# RLC_renonant.net
KiCad netlist of a schematic drawn in Altium Designer
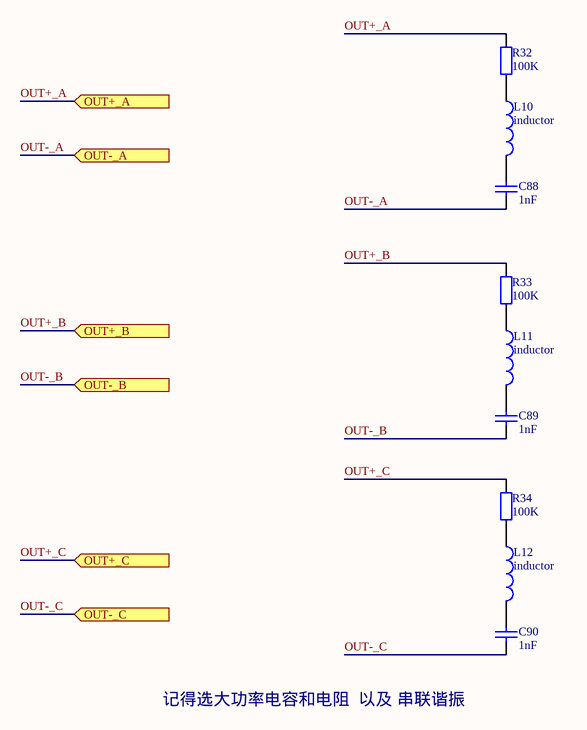
[diagram p0: RLC_renonant.SchDoc]

(export (version "E")
  (design (tool "Eeschema 10.0.6"))
  (components
    (comp (ref "C88") (value "1nF") (footprint "RAD-0.2") (libsource (lib "MyLibrary") (part "Cap")))
    (comp (ref "C89") (value "1nF") (footprint "RAD-0.2") (libsource (lib "MyLibrary") (part "Cap")))
    (comp (ref "C90") (value "1nF") (footprint "RAD-0.2") (libsource (lib "MyLibrary") (part "Cap")))
    (comp (ref "L10") (value "inductor") (footprint "inductor") (libsource (lib "Dugu") (part "inductor")))
    (comp (ref "L11") (value "inductor") (footprint "inductor") (libsource (lib "Dugu") (part "inductor")))
    (comp (ref "L12") (value "inductor") (footprint "inductor") (libsource (lib "Dugu") (part "inductor")))
    (comp (ref "R32")
      (value "100K")
      (footprint "Res_big")
      (fields
        (field (name "Comment") "Res")
        (field (name "原理图绘制者") "刘永钦")
        (field (name "原理图提供者") "刘永钦")
        (field (name "原理图审核人1") "徐鹏飞")
        (field (name "封装0805绘制者") "刘永钦")
        (field (name "封装0805提供者") "刘永钦")
        (field (name "封装0805审核人1") "徐鹏飞")
        (field (name "原理图审核人2") "朱觉文")
        (field (name "封装0805审核人2") "朱觉文")
        (field (name "封装0603提供者") "刘永钦")
        (field (name "封装0603审核人2") "朱觉文")
        (field (name "封装0603审核人1") "徐鹏飞")
        (field (name "封装2512-RESC6332X06N审核人2") "朱觉文")
        (field (name "封装2512-RESC6332X06N提供者") "刘永钦")
        (field (name "封装2512-RESC6332X06N审核人1") "徐鹏飞")
        (field (name "封装0603绘制者") "刘永钦")
        (field (name "封装2512-RESC6332X06N绘制者") "刘永钦")
      )
      (libsource (lib "DuGu") (part "Res"))
    )
    (comp (ref "R33")
      (value "100K")
      (footprint "Res_big")
      (fields
        (field (name "Comment") "Res")
        (field (name "原理图绘制者") "刘永钦")
        (field (name "原理图提供者") "刘永钦")
        (field (name "原理图审核人1") "徐鹏飞")
        (field (name "封装0805绘制者") "刘永钦")
        (field (name "封装0805提供者") "刘永钦")
        (field (name "封装0805审核人1") "徐鹏飞")
        (field (name "原理图审核人2") "朱觉文")
        (field (name "封装0805审核人2") "朱觉文")
        (field (name "封装0603提供者") "刘永钦")
        (field (name "封装0603审核人2") "朱觉文")
        (field (name "封装0603审核人1") "徐鹏飞")
        (field (name "封装2512-RESC6332X06N审核人2") "朱觉文")
        (field (name "封装2512-RESC6332X06N提供者") "刘永钦")
        (field (name "封装2512-RESC6332X06N审核人1") "徐鹏飞")
        (field (name "封装0603绘制者") "刘永钦")
        (field (name "封装2512-RESC6332X06N绘制者") "刘永钦")
      )
      (libsource (lib "DuGu") (part "Res"))
    )
    (comp (ref "R34")
      (value "100K")
      (footprint "Res_big")
      (fields
        (field (name "Comment") "Res")
        (field (name "原理图绘制者") "刘永钦")
        (field (name "原理图提供者") "刘永钦")
        (field (name "原理图审核人1") "徐鹏飞")
        (field (name "封装0805绘制者") "刘永钦")
        (field (name "封装0805提供者") "刘永钦")
        (field (name "封装0805审核人1") "徐鹏飞")
        (field (name "原理图审核人2") "朱觉文")
        (field (name "封装0805审核人2") "朱觉文")
        (field (name "封装0603提供者") "刘永钦")
        (field (name "封装0603审核人2") "朱觉文")
        (field (name "封装0603审核人1") "徐鹏飞")
        (field (name "封装2512-RESC6332X06N审核人2") "朱觉文")
        (field (name "封装2512-RESC6332X06N提供者") "刘永钦")
        (field (name "封装2512-RESC6332X06N审核人1") "徐鹏飞")
        (field (name "封装0603绘制者") "刘永钦")
        (field (name "封装2512-RESC6332X06N绘制者") "刘永钦")
      )
      (libsource (lib "DuGu") (part "Res"))
    )
  )
  (nets
    (net (code "1") (name "/OUT+_A") (class "Default")
      (node (ref "R32") (pin "1") (pinfunction "1_1") (pintype "passive"))
    )
    (net (code "2") (name "/OUT+_B") (class "Default")
      (node (ref "R33") (pin "1") (pinfunction "1_1") (pintype "passive"))
    )
    (net (code "3") (name "/OUT+_C") (class "Default")
      (node (ref "R34") (pin "1") (pinfunction "1_1") (pintype "passive"))
    )
    (net (code "4") (name "/OUT-_A") (class "Default")
      (node (ref "C88") (pin "1") (pinfunction "1_1") (pintype "passive"))
    )
    (net (code "5") (name "/OUT-_B") (class "Default")
      (node (ref "C89") (pin "1") (pinfunction "1_1") (pintype "passive"))
    )
    (net (code "6") (name "/OUT-_C") (class "Default")
      (node (ref "C90") (pin "1") (pinfunction "1_1") (pintype "passive"))
    )
    (net (code "7") (name "Net-(C88-Pad2)") (class "Default")
      (node (ref "C88") (pin "2") (pinfunction "2_2") (pintype "passive"))
      (node (ref "L10") (pin "2") (pinfunction "2_2") (pintype "passive"))
    )
    (net (code "8") (name "Net-(C89-Pad2)") (class "Default")
      (node (ref "C89") (pin "2") (pinfunction "2_2") (pintype "passive"))
      (node (ref "L11") (pin "2") (pinfunction "2_2") (pintype "passive"))
    )
    (net (code "9") (name "Net-(C90-Pad2)") (class "Default")
      (node (ref "C90") (pin "2") (pinfunction "2_2") (pintype "passive"))
      (node (ref "L12") (pin "2") (pinfunction "2_2") (pintype "passive"))
    )
    (net (code "10") (name "Net-(L10-Pad1)") (class "Default")
      (node (ref "L10") (pin "1") (pinfunction "1_1") (pintype "passive"))
      (node (ref "R32") (pin "2") (pinfunction "2_2") (pintype "passive"))
    )
    (net (code "11") (name "Net-(L11-Pad1)") (class "Default")
      (node (ref "L11") (pin "1") (pinfunction "1_1") (pintype "passive"))
      (node (ref "R33") (pin "2") (pinfunction "2_2") (pintype "passive"))
    )
    (net (code "12") (name "Net-(L12-Pad1)") (class "Default")
      (node (ref "L12") (pin "1") (pinfunction "1_1") (pintype "passive"))
      (node (ref "R34") (pin "2") (pinfunction "2_2") (pintype "passive"))
    )
  )
)
